# sensors_sht4x_sgp4x_bme68x.net
KiCad netlist of a schematic drawn in EAGLE
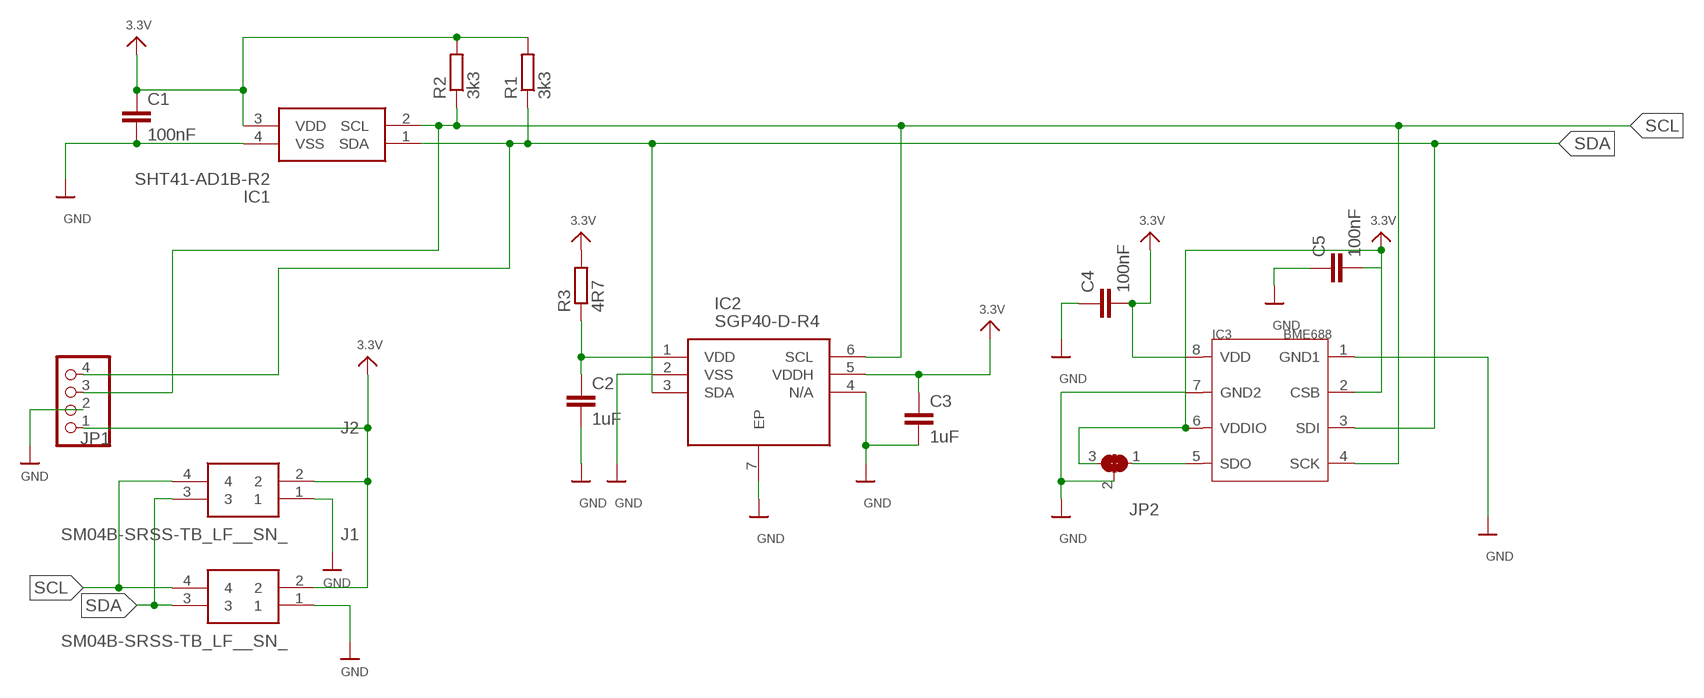
[diagram p0: schematic, sheet 1]

(export (version "E")
  (design (tool "Eeschema 10.0.6"))
  (components
    (comp (ref "C1")
      (value "100nF")
      (footprint "eagle-import:C0805")
      (libsource (lib "eagle-import") (part "C-EUC0805"))
    )
    (comp (ref "C2")
      (value "1uF")
      (footprint "eagle-import:C0805")
      (libsource (lib "eagle-import") (part "C-EUC0805"))
    )
    (comp (ref "C3")
      (value "1uF")
      (footprint "eagle-import:C0805")
      (libsource (lib "eagle-import") (part "C-EUC0805"))
    )
    (comp (ref "C4")
      (value "100nF")
      (footprint "eagle-import:C0805")
      (libsource (lib "eagle-import") (part "C-EUC0805"))
    )
    (comp (ref "C5")
      (value "100nF")
      (footprint "eagle-import:C0805")
      (libsource (lib "eagle-import") (part "C-EUC0805"))
    )
    (comp (ref "IC1")
      (value "SHT41-AD1B-R2")
      (footprint "eagle-import:SHT41AD1BR2")
      (libsource (lib "eagle-import") (part "SHT41-AD1B-R2"))
    )
    (comp (ref "IC2")
      (value "SGP40-D-R4")
      (footprint "eagle-import:SON80P244X244X95-7N")
      (libsource (lib "eagle-import") (part "SGP40-D-R4"))
    )
    (comp (ref "IC3")
      (value "BME688")
      (footprint "eagle-import:SNR8-0.8-3X3X0.93MM")
      (libsource (lib "eagle-import") (part "BME688"))
    )
    (comp (ref "J1")
      (value "SM04B-SRSS-TB_LF__SN_")
      (footprint "eagle-import:SM04B-SRSS-TB(LFSN)")
      (fields (field (name "MANUFACTURER_PART_NUMBER") "SM04B-SRSS-TB(LF)(SN)"))
      (libsource (lib "eagle-import") (part "SM04B-SRSS-TB_LF__SN_"))
    )
    (comp (ref "J2")
      (value "SM04B-SRSS-TB_LF__SN_")
      (footprint "eagle-import:SM04B-SRSS-TB(LFSN)")
      (fields (field (name "MANUFACTURER_PART_NUMBER") "SM04B-SRSS-TB(LF)(SN)"))
      (libsource (lib "eagle-import") (part "SM04B-SRSS-TB_LF__SN_"))
    )
    (comp (ref "JP1")
      (value "PINHD-1X4")
      (footprint "eagle-import:1X04")
      (libsource (lib "eagle-import") (part "PINHD-1X4"))
    )
    (comp (ref "JP2")
      (value "SOLDERJUMPER_2WAY0603")
      (footprint "eagle-import:SOLDERJUMPER_2WAY_OPEN_0603")
      (libsource (lib "eagle-import") (part "SOLDERJUMPER_2WAY0603"))
    )
    (comp (ref "R1")
      (value "3k3")
      (footprint "eagle-import:R0805")
      (libsource (lib "eagle-import") (part "R-EU_R0805"))
    )
    (comp (ref "R2")
      (value "3k3")
      (footprint "eagle-import:R0805")
      (libsource (lib "eagle-import") (part "R-EU_R0805"))
    )
    (comp (ref "R3")
      (value "4R7")
      (footprint "eagle-import:R0805")
      (libsource (lib "eagle-import") (part "R-EU_R0805"))
    )
  )
  (nets
    (net (code "1") (name "3.3V") (class "Default")
      (node (ref "C1") (pin "1") (pinfunction "1_1") (pintype "passive"))
      (node (ref "C3") (pin "1") (pinfunction "1_1") (pintype "passive"))
      (node (ref "C4") (pin "2") (pinfunction "2_2") (pintype "passive"))
      (node (ref "C5") (pin "2") (pinfunction "2_2") (pintype "passive"))
      (node (ref "IC1") (pin "3") (pinfunction "VDD_3") (pintype "bidirectional"))
      (node (ref "IC2") (pin "5") (pinfunction "VDDH_5") (pintype "bidirectional"))
      (node (ref "IC3") (pin "2") (pinfunction "CSB_2") (pintype "bidirectional"))
      (node (ref "IC3") (pin "6") (pinfunction "VDDIO_6") (pintype "bidirectional"))
      (node (ref "IC3") (pin "8") (pinfunction "VDD_8") (pintype "bidirectional"))
      (node (ref "J1") (pin "2") (pinfunction "2_2") (pintype "bidirectional"))
      (node (ref "J2") (pin "2") (pinfunction "2_2") (pintype "bidirectional"))
      (node (ref "JP1") (pin "1") (pinfunction "1_1") (pintype "passive"))
      (node (ref "JP2") (pin "3") (pinfunction "3_3") (pintype "passive"))
      (node (ref "R1") (pin "2") (pinfunction "2_2") (pintype "passive"))
      (node (ref "R2") (pin "2") (pinfunction "2_2") (pintype "passive"))
      (node (ref "R3") (pin "2") (pinfunction "2_2") (pintype "passive"))
    )
    (net (code "2") (name "GND") (class "Default")
      (node (ref "C1") (pin "2") (pinfunction "2_2") (pintype "passive"))
      (node (ref "C2") (pin "2") (pinfunction "2_2") (pintype "passive"))
      (node (ref "C3") (pin "2") (pinfunction "2_2") (pintype "passive"))
      (node (ref "C4") (pin "1") (pinfunction "1_1") (pintype "passive"))
      (node (ref "C5") (pin "1") (pinfunction "1_1") (pintype "passive"))
      (node (ref "IC1") (pin "4") (pinfunction "VSS_4") (pintype "bidirectional"))
      (node (ref "IC2") (pin "2") (pinfunction "VSS_2") (pintype "bidirectional"))
      (node (ref "IC2") (pin "4") (pinfunction "N/A_4") (pintype "bidirectional"))
      (node (ref "IC2") (pin "7") (pinfunction "EP_7") (pintype "bidirectional"))
      (node (ref "IC3") (pin "1") (pinfunction "GND1_1") (pintype "bidirectional"))
      (node (ref "IC3") (pin "7") (pinfunction "GND2_7") (pintype "bidirectional"))
      (node (ref "J1") (pin "1") (pinfunction "1_1") (pintype "bidirectional"))
      (node (ref "J2") (pin "1") (pinfunction "1_1") (pintype "bidirectional"))
      (node (ref "JP1") (pin "2") (pinfunction "2_2") (pintype "passive"))
      (node (ref "JP2") (pin "2") (pinfunction "2_2") (pintype "passive"))
    )
    (net (code "3") (name "Net-(IC2-VDD)") (class "Default")
      (node (ref "C2") (pin "1") (pinfunction "1_1") (pintype "passive"))
      (node (ref "IC2") (pin "1") (pinfunction "VDD_1") (pintype "bidirectional"))
      (node (ref "R3") (pin "1") (pinfunction "1_1") (pintype "passive"))
    )
    (net (code "4") (name "Net-(IC3-SDO)") (class "Default")
      (node (ref "IC3") (pin "5") (pinfunction "SDO_5") (pintype "bidirectional"))
      (node (ref "JP2") (pin "1") (pinfunction "1_1") (pintype "passive"))
    )
    (net (code "5") (name "SCL") (class "Default")
      (node (ref "IC1") (pin "2") (pinfunction "SCL_2") (pintype "bidirectional"))
      (node (ref "IC2") (pin "6") (pinfunction "SCL_6") (pintype "bidirectional"))
      (node (ref "IC3") (pin "4") (pinfunction "SCK_4") (pintype "bidirectional"))
      (node (ref "J1") (pin "4") (pinfunction "4_4") (pintype "bidirectional"))
      (node (ref "J2") (pin "4") (pinfunction "4_4") (pintype "bidirectional"))
      (node (ref "JP1") (pin "3") (pinfunction "3_3") (pintype "passive"))
      (node (ref "R2") (pin "1") (pinfunction "1_1") (pintype "passive"))
    )
    (net (code "6") (name "SDA") (class "Default")
      (node (ref "IC1") (pin "1") (pinfunction "SDA_1") (pintype "bidirectional"))
      (node (ref "IC2") (pin "3") (pinfunction "SDA_3") (pintype "bidirectional"))
      (node (ref "IC3") (pin "3") (pinfunction "SDI_3") (pintype "bidirectional"))
      (node (ref "J1") (pin "3") (pinfunction "3_3") (pintype "bidirectional"))
      (node (ref "J2") (pin "3") (pinfunction "3_3") (pintype "bidirectional"))
      (node (ref "JP1") (pin "4") (pinfunction "4_4") (pintype "passive"))
      (node (ref "R1") (pin "1") (pinfunction "1_1") (pintype "passive"))
    )
  )
)
